# wendor_arduino.net
KiCad netlist of a schematic drawn in EAGLE
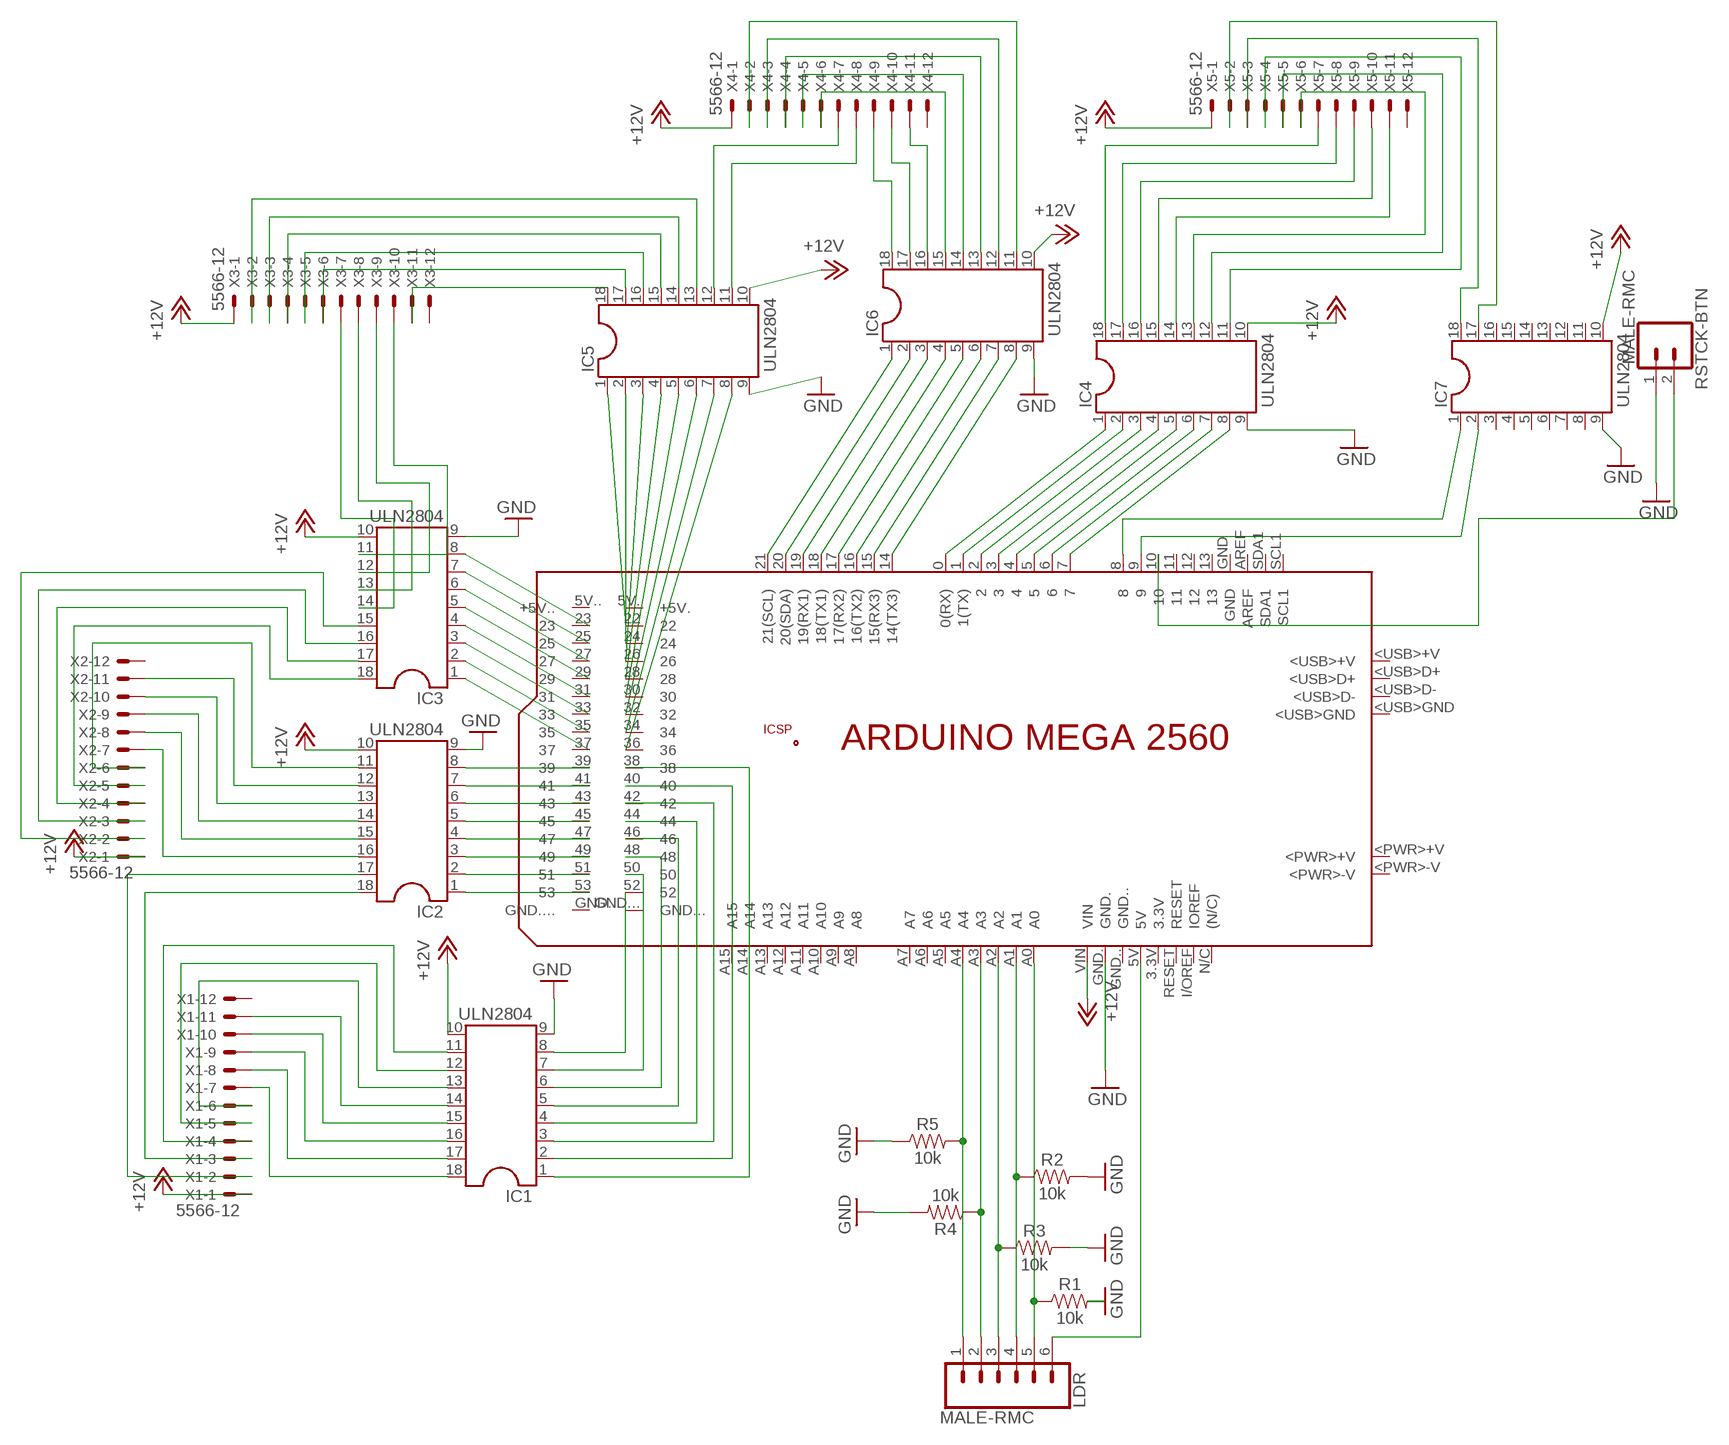
[diagram p0: schematic, sheet 1]

(export (version "E")
  (design (tool "Eeschema 10.0.6"))
  (components
    (comp (ref "IC1")
      (value "ULN2804")
      (footprint "eagle-import:SOCKET-18")
      (libsource (lib "eagle-import") (part "DIL18S"))
    )
    (comp (ref "IC2")
      (value "ULN2804")
      (footprint "eagle-import:SOCKET-18")
      (libsource (lib "eagle-import") (part "DIL18S"))
    )
    (comp (ref "IC3")
      (value "ULN2804")
      (footprint "eagle-import:SOCKET-18")
      (libsource (lib "eagle-import") (part "DIL18S"))
    )
    (comp (ref "IC4")
      (value "ULN2804")
      (footprint "eagle-import:SOCKET-18")
      (libsource (lib "eagle-import") (part "DIL18S"))
    )
    (comp (ref "IC5")
      (value "ULN2804")
      (footprint "eagle-import:SOCKET-18")
      (libsource (lib "eagle-import") (part "DIL18S"))
    )
    (comp (ref "IC6")
      (value "ULN2804")
      (footprint "eagle-import:SOCKET-18")
      (libsource (lib "eagle-import") (part "DIL18S"))
    )
    (comp (ref "IC7")
      (value "ULN2804")
      (footprint "eagle-import:SOCKET-18")
      (libsource (lib "eagle-import") (part "DIL18S"))
    )
    (comp (ref "LDR")
      (value "MALE-RMC")
      (footprint "eagle-import:1X06")
      (libsource (lib "eagle-import") (part "CONN_06SILK_FEMALE_PTH"))
    )
    (comp (ref "PCB1")
      (value "ARDUINO_MEGA2560")
      (footprint "eagle-import:ARDUINO_MEGA2560")
      (libsource (lib "eagle-import") (part "ARDUINO_MEGA2560"))
    )
    (comp (ref "R1")
      (value "10k")
      (footprint "eagle-import:AXIAL-0.3")
      (libsource (lib "eagle-import") (part "10KOHM-HORIZ-1/4W-1%"))
    )
    (comp (ref "R2")
      (value "10k")
      (footprint "eagle-import:AXIAL-0.3")
      (libsource (lib "eagle-import") (part "10KOHM-HORIZ-1/4W-1%"))
    )
    (comp (ref "R3")
      (value "10k")
      (footprint "eagle-import:AXIAL-0.3")
      (libsource (lib "eagle-import") (part "10KOHM-HORIZ-1/4W-1%"))
    )
    (comp (ref "R4")
      (value "10k")
      (footprint "eagle-import:AXIAL-0.3")
      (libsource (lib "eagle-import") (part "10KOHM-HORIZ-1/4W-1%"))
    )
    (comp (ref "R5")
      (value "10k")
      (footprint "eagle-import:AXIAL-0.3")
      (libsource (lib "eagle-import") (part "10KOHM-HORIZ-1/4W-1%"))
    )
    (comp (ref "RSTCK-BTN")
      (value "MALE-RMC")
      (footprint "eagle-import:1X02")
      (libsource (lib "eagle-import") (part "CONN_02"))
    )
    (comp (ref "X1")
      (value "5566-12")
      (footprint "eagle-import:5566-12")
      (fields (field (name "MF") "MOLEX"))
      (libsource (lib "eagle-import") (part "5566-12"))
    )
    (comp (ref "X2")
      (value "5566-12")
      (footprint "eagle-import:5566-12")
      (fields (field (name "MF") "MOLEX"))
      (libsource (lib "eagle-import") (part "5566-12"))
    )
    (comp (ref "X3")
      (value "5566-12")
      (footprint "eagle-import:5566-12")
      (fields (field (name "MF") "MOLEX"))
      (libsource (lib "eagle-import") (part "5566-12"))
    )
    (comp (ref "X4")
      (value "5566-12")
      (footprint "eagle-import:5566-12")
      (fields (field (name "MF") "MOLEX"))
      (libsource (lib "eagle-import") (part "5566-12"))
    )
    (comp (ref "X5")
      (value "5566-12")
      (footprint "eagle-import:5566-12")
      (fields (field (name "MF") "MOLEX"))
      (libsource (lib "eagle-import") (part "5566-12"))
    )
  )
  (nets
    (net (code "1") (name "+12V") (class "Default")
      (node (ref "IC1") (pin "10") (pinfunction "10_10") (pintype "passive"))
      (node (ref "IC2") (pin "10") (pinfunction "10_10") (pintype "passive"))
      (node (ref "IC3") (pin "10") (pinfunction "10_10") (pintype "passive"))
      (node (ref "IC4") (pin "10") (pinfunction "10_10") (pintype "passive"))
      (node (ref "IC5") (pin "10") (pinfunction "10_10") (pintype "passive"))
      (node (ref "IC6") (pin "10") (pinfunction "10_10") (pintype "passive"))
      (node (ref "IC7") (pin "10") (pinfunction "10_10") (pintype "passive"))
      (node (ref "PCB1") (pin "VIN") (pinfunction "VIN_VIN") (pintype "bidirectional"))
      (node (ref "X1") (pin "1") (pinfunction "S_1") (pintype "passive"))
      (node (ref "X2") (pin "1") (pinfunction "S_1") (pintype "passive"))
      (node (ref "X3") (pin "1") (pinfunction "S_1") (pintype "passive"))
      (node (ref "X4") (pin "1") (pinfunction "S_1") (pintype "passive"))
      (node (ref "X5") (pin "1") (pinfunction "S_1") (pintype "passive"))
    )
    (net (code "2") (name "GND") (class "Default")
      (node (ref "IC1") (pin "9") (pinfunction "9_9") (pintype "passive"))
      (node (ref "IC2") (pin "9") (pinfunction "9_9") (pintype "passive"))
      (node (ref "IC3") (pin "9") (pinfunction "9_9") (pintype "passive"))
      (node (ref "IC4") (pin "9") (pinfunction "9_9") (pintype "passive"))
      (node (ref "IC5") (pin "9") (pinfunction "9_9") (pintype "passive"))
      (node (ref "IC6") (pin "9") (pinfunction "9_9") (pintype "passive"))
      (node (ref "IC7") (pin "9") (pinfunction "9_9") (pintype "passive"))
      (node (ref "PCB1") (pin "GND.") (pinfunction "GND._GND.") (pintype "bidirectional"))
      (node (ref "R1") (pin "P$2") (pinfunction "2_P$2") (pintype "passive"))
      (node (ref "R2") (pin "P$2") (pinfunction "2_P$2") (pintype "passive"))
      (node (ref "R3") (pin "P$2") (pinfunction "2_P$2") (pintype "passive"))
      (node (ref "R4") (pin "P$2") (pinfunction "2_P$2") (pintype "passive"))
      (node (ref "R5") (pin "P$1") (pinfunction "1_P$1") (pintype "passive"))
      (node (ref "RSTCK-BTN") (pin "1") (pinfunction "1_1") (pintype "passive"))
    )
    (net (code "3") (name "Net-(IC1-Pad1)") (class "Default")
      (node (ref "IC1") (pin "1") (pinfunction "1_1") (pintype "passive"))
      (node (ref "PCB1") (pin "38") (pinfunction "38_38") (pintype "bidirectional"))
    )
    (net (code "4") (name "Net-(IC1-Pad2)") (class "Default")
      (node (ref "IC1") (pin "2") (pinfunction "2_2") (pintype "passive"))
      (node (ref "PCB1") (pin "40") (pinfunction "40_40") (pintype "bidirectional"))
    )
    (net (code "5") (name "Net-(IC1-Pad3)") (class "Default")
      (node (ref "IC1") (pin "3") (pinfunction "3_3") (pintype "passive"))
      (node (ref "PCB1") (pin "42") (pinfunction "42_42") (pintype "bidirectional"))
    )
    (net (code "6") (name "Net-(IC1-Pad4)") (class "Default")
      (node (ref "IC1") (pin "4") (pinfunction "4_4") (pintype "passive"))
      (node (ref "PCB1") (pin "44") (pinfunction "44_44") (pintype "bidirectional"))
    )
    (net (code "7") (name "Net-(IC1-Pad5)") (class "Default")
      (node (ref "IC1") (pin "5") (pinfunction "5_5") (pintype "passive"))
      (node (ref "PCB1") (pin "46") (pinfunction "46_46") (pintype "bidirectional"))
    )
    (net (code "8") (name "Net-(IC1-Pad6)") (class "Default")
      (node (ref "IC1") (pin "6") (pinfunction "6_6") (pintype "passive"))
      (node (ref "PCB1") (pin "48") (pinfunction "48_48") (pintype "bidirectional"))
    )
    (net (code "9") (name "Net-(IC1-Pad7)") (class "Default")
      (node (ref "IC1") (pin "7") (pinfunction "7_7") (pintype "passive"))
      (node (ref "PCB1") (pin "50") (pinfunction "50_50") (pintype "bidirectional"))
    )
    (net (code "10") (name "Net-(IC1-Pad8)") (class "Default")
      (node (ref "IC1") (pin "8") (pinfunction "8_8") (pintype "passive"))
      (node (ref "PCB1") (pin "52") (pinfunction "52_52") (pintype "bidirectional"))
    )
    (net (code "11") (name "Net-(IC2-Pad1)") (class "Default")
      (node (ref "IC2") (pin "1") (pinfunction "1_1") (pintype "passive"))
      (node (ref "PCB1") (pin "53") (pinfunction "53_53") (pintype "bidirectional"))
    )
    (net (code "12") (name "Net-(IC2-Pad2)") (class "Default")
      (node (ref "IC2") (pin "2") (pinfunction "2_2") (pintype "passive"))
      (node (ref "PCB1") (pin "51") (pinfunction "51_51") (pintype "bidirectional"))
    )
    (net (code "13") (name "Net-(IC2-Pad3)") (class "Default")
      (node (ref "IC2") (pin "3") (pinfunction "3_3") (pintype "passive"))
      (node (ref "PCB1") (pin "49") (pinfunction "49_49") (pintype "bidirectional"))
    )
    (net (code "14") (name "Net-(IC2-Pad4)") (class "Default")
      (node (ref "IC2") (pin "4") (pinfunction "4_4") (pintype "passive"))
      (node (ref "PCB1") (pin "47") (pinfunction "47_47") (pintype "bidirectional"))
    )
    (net (code "15") (name "Net-(IC2-Pad5)") (class "Default")
      (node (ref "IC2") (pin "5") (pinfunction "5_5") (pintype "passive"))
      (node (ref "PCB1") (pin "45") (pinfunction "45_45") (pintype "bidirectional"))
    )
    (net (code "16") (name "Net-(IC2-Pad6)") (class "Default")
      (node (ref "IC2") (pin "6") (pinfunction "6_6") (pintype "passive"))
      (node (ref "PCB1") (pin "43") (pinfunction "43_43") (pintype "bidirectional"))
    )
    (net (code "17") (name "Net-(IC2-Pad7)") (class "Default")
      (node (ref "IC2") (pin "7") (pinfunction "7_7") (pintype "passive"))
      (node (ref "PCB1") (pin "41") (pinfunction "41_41") (pintype "bidirectional"))
    )
    (net (code "18") (name "Net-(IC2-Pad8)") (class "Default")
      (node (ref "IC2") (pin "8") (pinfunction "8_8") (pintype "passive"))
      (node (ref "PCB1") (pin "39") (pinfunction "39_39") (pintype "bidirectional"))
    )
    (net (code "19") (name "Net-(IC3-Pad1)") (class "Default")
      (node (ref "IC3") (pin "1") (pinfunction "1_1") (pintype "passive"))
      (node (ref "PCB1") (pin "37") (pinfunction "37_37") (pintype "bidirectional"))
    )
    (net (code "20") (name "Net-(IC3-Pad2)") (class "Default")
      (node (ref "IC3") (pin "2") (pinfunction "2_2") (pintype "passive"))
      (node (ref "PCB1") (pin "35") (pinfunction "35_35") (pintype "bidirectional"))
    )
    (net (code "21") (name "Net-(IC3-Pad3)") (class "Default")
      (node (ref "IC3") (pin "3") (pinfunction "3_3") (pintype "passive"))
      (node (ref "PCB1") (pin "33") (pinfunction "33_33") (pintype "bidirectional"))
    )
    (net (code "22") (name "Net-(IC3-Pad4)") (class "Default")
      (node (ref "IC3") (pin "4") (pinfunction "4_4") (pintype "passive"))
      (node (ref "PCB1") (pin "31") (pinfunction "31_31") (pintype "bidirectional"))
    )
    (net (code "23") (name "Net-(IC3-Pad5)") (class "Default")
      (node (ref "IC3") (pin "5") (pinfunction "5_5") (pintype "passive"))
      (node (ref "PCB1") (pin "29") (pinfunction "29_29") (pintype "bidirectional"))
    )
    (net (code "24") (name "Net-(IC3-Pad6)") (class "Default")
      (node (ref "IC3") (pin "6") (pinfunction "6_6") (pintype "passive"))
      (node (ref "PCB1") (pin "27") (pinfunction "27_27") (pintype "bidirectional"))
    )
    (net (code "25") (name "Net-(IC3-Pad7)") (class "Default")
      (node (ref "IC3") (pin "7") (pinfunction "7_7") (pintype "passive"))
      (node (ref "PCB1") (pin "25") (pinfunction "25_25") (pintype "bidirectional"))
    )
    (net (code "26") (name "Net-(IC3-Pad8)") (class "Default")
      (node (ref "IC3") (pin "8") (pinfunction "8_8") (pintype "passive"))
      (node (ref "PCB1") (pin "23") (pinfunction "23_23") (pintype "bidirectional"))
    )
    (net (code "27") (name "Net-(IC4-Pad3)") (class "Default")
      (node (ref "IC4") (pin "3") (pinfunction "3_3") (pintype "passive"))
      (node (ref "PCB1") (pin "2") (pinfunction "2_2") (pintype "bidirectional"))
    )
    (net (code "28") (name "Net-(IC4-Pad4)") (class "Default")
      (node (ref "IC4") (pin "4") (pinfunction "4_4") (pintype "passive"))
      (node (ref "PCB1") (pin "3") (pinfunction "3_3") (pintype "bidirectional"))
    )
    (net (code "29") (name "Net-(IC4-Pad5)") (class "Default")
      (node (ref "IC4") (pin "5") (pinfunction "5_5") (pintype "passive"))
      (node (ref "PCB1") (pin "4") (pinfunction "4_4") (pintype "bidirectional"))
    )
    (net (code "30") (name "Net-(IC4-Pad6)") (class "Default")
      (node (ref "IC4") (pin "6") (pinfunction "6_6") (pintype "passive"))
      (node (ref "PCB1") (pin "5") (pinfunction "5_5") (pintype "bidirectional"))
    )
    (net (code "31") (name "Net-(IC4-Pad7)") (class "Default")
      (node (ref "IC4") (pin "7") (pinfunction "7_7") (pintype "passive"))
      (node (ref "PCB1") (pin "6") (pinfunction "6_6") (pintype "bidirectional"))
    )
    (net (code "32") (name "Net-(IC4-Pad8)") (class "Default")
      (node (ref "IC4") (pin "8") (pinfunction "8_8") (pintype "passive"))
      (node (ref "PCB1") (pin "7") (pinfunction "7_7") (pintype "bidirectional"))
    )
    (net (code "33") (name "Net-(IC5-Pad1)") (class "Default")
      (node (ref "IC5") (pin "1") (pinfunction "1_1") (pintype "passive"))
      (node (ref "PCB1") (pin "22") (pinfunction "22_22") (pintype "bidirectional"))
    )
    (net (code "34") (name "Net-(IC5-Pad2)") (class "Default")
      (node (ref "IC5") (pin "2") (pinfunction "2_2") (pintype "passive"))
      (node (ref "PCB1") (pin "24") (pinfunction "24_24") (pintype "bidirectional"))
    )
    (net (code "35") (name "Net-(IC5-Pad3)") (class "Default")
      (node (ref "IC5") (pin "3") (pinfunction "3_3") (pintype "passive"))
      (node (ref "PCB1") (pin "26") (pinfunction "26_26") (pintype "bidirectional"))
    )
    (net (code "36") (name "Net-(IC5-Pad4)") (class "Default")
      (node (ref "IC5") (pin "4") (pinfunction "4_4") (pintype "passive"))
      (node (ref "PCB1") (pin "28") (pinfunction "28_28") (pintype "bidirectional"))
    )
    (net (code "37") (name "Net-(IC5-Pad5)") (class "Default")
      (node (ref "IC5") (pin "5") (pinfunction "5_5") (pintype "passive"))
      (node (ref "PCB1") (pin "30") (pinfunction "30_30") (pintype "bidirectional"))
    )
    (net (code "38") (name "Net-(IC5-Pad6)") (class "Default")
      (node (ref "IC5") (pin "6") (pinfunction "6_6") (pintype "passive"))
      (node (ref "PCB1") (pin "32") (pinfunction "32_32") (pintype "bidirectional"))
    )
    (net (code "39") (name "Net-(IC5-Pad7)") (class "Default")
      (node (ref "IC5") (pin "7") (pinfunction "7_7") (pintype "passive"))
      (node (ref "PCB1") (pin "34") (pinfunction "34_34") (pintype "bidirectional"))
    )
    (net (code "40") (name "Net-(IC5-Pad8)") (class "Default")
      (node (ref "IC5") (pin "8") (pinfunction "8_8") (pintype "passive"))
      (node (ref "PCB1") (pin "36") (pinfunction "36_36") (pintype "bidirectional"))
    )
    (net (code "41") (name "Net-(IC7-Pad1)") (class "Default")
      (node (ref "IC7") (pin "1") (pinfunction "1_1") (pintype "passive"))
      (node (ref "PCB1") (pin "8") (pinfunction "8_8") (pintype "bidirectional"))
    )
    (net (code "42") (name "Net-(IC7-Pad2)") (class "Default")
      (node (ref "IC7") (pin "2") (pinfunction "2_2") (pintype "passive"))
      (node (ref "PCB1") (pin "9") (pinfunction "9_9") (pintype "bidirectional"))
    )
    (net (code "43") (name "Net-(LDR-Pad6)") (class "Default")
      (node (ref "LDR") (pin "6") (pinfunction "6_6") (pintype "passive"))
      (node (ref "PCB1") (pin "5V") (pinfunction "5V_5V") (pintype "bidirectional"))
    )
    (net (code "44") (name "Net-(PCB1-0(RX))") (class "Default")
      (node (ref "IC4") (pin "1") (pinfunction "1_1") (pintype "passive"))
      (node (ref "PCB1") (pin "0") (pinfunction "0(RX)_0") (pintype "bidirectional"))
    )
    (net (code "45") (name "Net-(PCB1-1(TX))") (class "Default")
      (node (ref "IC4") (pin "2") (pinfunction "2_2") (pintype "passive"))
      (node (ref "PCB1") (pin "1") (pinfunction "1(TX)_1") (pintype "bidirectional"))
    )
    (net (code "46") (name "Net-(PCB1-14(TX3))") (class "Default")
      (node (ref "IC6") (pin "8") (pinfunction "8_8") (pintype "passive"))
      (node (ref "PCB1") (pin "14") (pinfunction "14(TX3)_14") (pintype "bidirectional"))
    )
    (net (code "47") (name "Net-(PCB1-15(RX3))") (class "Default")
      (node (ref "IC6") (pin "7") (pinfunction "7_7") (pintype "passive"))
      (node (ref "PCB1") (pin "15") (pinfunction "15(RX3)_15") (pintype "bidirectional"))
    )
    (net (code "48") (name "Net-(PCB1-16(TX2))") (class "Default")
      (node (ref "IC6") (pin "6") (pinfunction "6_6") (pintype "passive"))
      (node (ref "PCB1") (pin "16") (pinfunction "16(TX2)_16") (pintype "bidirectional"))
    )
    (net (code "49") (name "Net-(PCB1-17(RX2))") (class "Default")
      (node (ref "IC6") (pin "5") (pinfunction "5_5") (pintype "passive"))
      (node (ref "PCB1") (pin "17") (pinfunction "17(RX2)_17") (pintype "bidirectional"))
    )
    (net (code "50") (name "Net-(PCB1-18(TX1))") (class "Default")
      (node (ref "IC6") (pin "4") (pinfunction "4_4") (pintype "passive"))
      (node (ref "PCB1") (pin "18") (pinfunction "18(TX1)_18") (pintype "bidirectional"))
    )
    (net (code "51") (name "Net-(PCB1-19(RX1))") (class "Default")
      (node (ref "IC6") (pin "3") (pinfunction "3_3") (pintype "passive"))
      (node (ref "PCB1") (pin "19") (pinfunction "19(RX1)_19") (pintype "bidirectional"))
    )
    (net (code "52") (name "Net-(PCB1-20(SDA))") (class "Default")
      (node (ref "IC6") (pin "2") (pinfunction "2_2") (pintype "passive"))
      (node (ref "PCB1") (pin "20") (pinfunction "20(SDA)_20") (pintype "bidirectional"))
    )
    (net (code "53") (name "Net-(PCB1-21(SCL))") (class "Default")
      (node (ref "IC6") (pin "1") (pinfunction "1_1") (pintype "passive"))
      (node (ref "PCB1") (pin "21") (pinfunction "21(SCL)_21") (pintype "bidirectional"))
    )
    (net (code "54") (name "Net-(PCB1-Pad10)") (class "Default")
      (node (ref "PCB1") (pin "10") (pinfunction "10_10") (pintype "bidirectional"))
      (node (ref "RSTCK-BTN") (pin "2") (pinfunction "2_2") (pintype "passive"))
    )
    (net (code "55") (name "Net-(R1-1)") (class "Default")
      (node (ref "LDR") (pin "5") (pinfunction "5_5") (pintype "passive"))
      (node (ref "PCB1") (pin "A0") (pinfunction "A0_A0") (pintype "bidirectional"))
      (node (ref "R1") (pin "P$1") (pinfunction "1_P$1") (pintype "passive"))
    )
    (net (code "56") (name "Net-(R2-1)") (class "Default")
      (node (ref "LDR") (pin "4") (pinfunction "4_4") (pintype "passive"))
      (node (ref "PCB1") (pin "A1") (pinfunction "A1_A1") (pintype "bidirectional"))
      (node (ref "R2") (pin "P$1") (pinfunction "1_P$1") (pintype "passive"))
    )
    (net (code "57") (name "Net-(R3-1)") (class "Default")
      (node (ref "LDR") (pin "3") (pinfunction "3_3") (pintype "passive"))
      (node (ref "PCB1") (pin "A2") (pinfunction "A2_A2") (pintype "bidirectional"))
      (node (ref "R3") (pin "P$1") (pinfunction "1_P$1") (pintype "passive"))
    )
    (net (code "58") (name "Net-(R4-1)") (class "Default")
      (node (ref "LDR") (pin "2") (pinfunction "2_2") (pintype "passive"))
      (node (ref "PCB1") (pin "A3") (pinfunction "A3_A3") (pintype "bidirectional"))
      (node (ref "R4") (pin "P$1") (pinfunction "1_P$1") (pintype "passive"))
    )
    (net (code "59") (name "Net-(R5-2)") (class "Default")
      (node (ref "LDR") (pin "1") (pinfunction "1_1") (pintype "passive"))
      (node (ref "PCB1") (pin "A4") (pinfunction "A4_A4") (pintype "bidirectional"))
      (node (ref "R5") (pin "P$2") (pinfunction "2_P$2") (pintype "passive"))
    )
    (net (code "60") (name "Net-(X1B-S)") (class "Default")
      (node (ref "IC1") (pin "15") (pinfunction "15_15") (pintype "passive"))
      (node (ref "X1") (pin "10") (pinfunction "S_10") (pintype "passive"))
    )
    (net (code "61") (name "Net-(X1C-S)") (class "Default")
      (node (ref "IC1") (pin "14") (pinfunction "14_14") (pintype "passive"))
      (node (ref "X1") (pin "11") (pinfunction "S_11") (pintype "passive"))
    )
    (net (code "62") (name "Net-(X1E-S)") (class "Default")
      (node (ref "IC2") (pin "17") (pinfunction "17_17") (pintype "passive"))
      (node (ref "X1") (pin "2") (pinfunction "S_2") (pintype "passive"))
    )
    (net (code "63") (name "Net-(X1F-S)") (class "Default")
      (node (ref "IC2") (pin "18") (pinfunction "18_18") (pintype "passive"))
      (node (ref "X1") (pin "3") (pinfunction "S_3") (pintype "passive"))
    )
    (net (code "64") (name "Net-(X1G-S)") (class "Default")
      (node (ref "IC1") (pin "11") (pinfunction "11_11") (pintype "passive"))
      (node (ref "X1") (pin "4") (pinfunction "S_4") (pintype "passive"))
    )
    (net (code "65") (name "Net-(X1H-S)") (class "Default")
      (node (ref "IC1") (pin "12") (pinfunction "12_12") (pintype "passive"))
      (node (ref "X1") (pin "5") (pinfunction "S_5") (pintype "passive"))
    )
    (net (code "66") (name "Net-(X1I-S)") (class "Default")
      (node (ref "IC1") (pin "13") (pinfunction "13_13") (pintype "passive"))
      (node (ref "X1") (pin "6") (pinfunction "S_6") (pintype "passive"))
    )
    (net (code "67") (name "Net-(X1J-S)") (class "Default")
      (node (ref "IC1") (pin "18") (pinfunction "18_18") (pintype "passive"))
      (node (ref "X1") (pin "7") (pinfunction "S_7") (pintype "passive"))
    )
    (net (code "68") (name "Net-(X1K-S)") (class "Default")
      (node (ref "IC1") (pin "17") (pinfunction "17_17") (pintype "passive"))
      (node (ref "X1") (pin "8") (pinfunction "S_8") (pintype "passive"))
    )
    (net (code "69") (name "Net-(X1L-S)") (class "Default")
      (node (ref "IC1") (pin "16") (pinfunction "16_16") (pintype "passive"))
      (node (ref "X1") (pin "9") (pinfunction "S_9") (pintype "passive"))
    )
    (net (code "70") (name "Net-(X2B-S)") (class "Default")
      (node (ref "IC2") (pin "13") (pinfunction "13_13") (pintype "passive"))
      (node (ref "X2") (pin "10") (pinfunction "S_10") (pintype "passive"))
    )
    (net (code "71") (name "Net-(X2C-S)") (class "Default")
      (node (ref "IC2") (pin "12") (pinfunction "12_12") (pintype "passive"))
      (node (ref "X2") (pin "11") (pinfunction "S_11") (pintype "passive"))
    )
    (net (code "72") (name "Net-(X2E-S)") (class "Default")
      (node (ref "IC3") (pin "15") (pinfunction "15_15") (pintype "passive"))
      (node (ref "X2") (pin "2") (pinfunction "S_2") (pintype "passive"))
    )
    (net (code "73") (name "Net-(X2F-S)") (class "Default")
      (node (ref "IC3") (pin "16") (pinfunction "16_16") (pintype "passive"))
      (node (ref "X2") (pin "3") (pinfunction "S_3") (pintype "passive"))
    )
    (net (code "74") (name "Net-(X2G-S)") (class "Default")
      (node (ref "IC3") (pin "17") (pinfunction "17_17") (pintype "passive"))
      (node (ref "X2") (pin "4") (pinfunction "S_4") (pintype "passive"))
    )
    (net (code "75") (name "Net-(X2H-S)") (class "Default")
      (node (ref "IC3") (pin "18") (pinfunction "18_18") (pintype "passive"))
      (node (ref "X2") (pin "5") (pinfunction "S_5") (pintype "passive"))
    )
    (net (code "76") (name "Net-(X2I-S)") (class "Default")
      (node (ref "IC2") (pin "11") (pinfunction "11_11") (pintype "passive"))
      (node (ref "X2") (pin "6") (pinfunction "S_6") (pintype "passive"))
    )
    (net (code "77") (name "Net-(X2J-S)") (class "Default")
      (node (ref "IC2") (pin "16") (pinfunction "16_16") (pintype "passive"))
      (node (ref "X2") (pin "7") (pinfunction "S_7") (pintype "passive"))
    )
    (net (code "78") (name "Net-(X2K-S)") (class "Default")
      (node (ref "IC2") (pin "15") (pinfunction "15_15") (pintype "passive"))
      (node (ref "X2") (pin "8") (pinfunction "S_8") (pintype "passive"))
    )
    (net (code "79") (name "Net-(X2L-S)") (class "Default")
      (node (ref "IC2") (pin "14") (pinfunction "14_14") (pintype "passive"))
      (node (ref "X2") (pin "9") (pinfunction "S_9") (pintype "passive"))
    )
    (net (code "80") (name "Net-(X3B-S)") (class "Default")
      (node (ref "IC3") (pin "11") (pinfunction "11_11") (pintype "passive"))
      (node (ref "X3") (pin "10") (pinfunction "S_10") (pintype "passive"))
    )
    (net (code "81") (name "Net-(X3C-S)") (class "Default")
      (node (ref "IC5") (pin "18") (pinfunction "18_18") (pintype "passive"))
      (node (ref "X3") (pin "11") (pinfunction "S_11") (pintype "passive"))
    )
    (net (code "82") (name "Net-(X3E-S)") (class "Default")
      (node (ref "IC5") (pin "13") (pinfunction "13_13") (pintype "passive"))
      (node (ref "X3") (pin "2") (pinfunction "S_2") (pintype "passive"))
    )
    (net (code "83") (name "Net-(X3F-S)") (class "Default")
      (node (ref "IC5") (pin "14") (pinfunction "14_14") (pintype "passive"))
      (node (ref "X3") (pin "3") (pinfunction "S_3") (pintype "passive"))
    )
    (net (code "84") (name "Net-(X3G-S)") (class "Default")
      (node (ref "IC5") (pin "15") (pinfunction "15_15") (pintype "passive"))
      (node (ref "X3") (pin "4") (pinfunction "S_4") (pintype "passive"))
    )
    (net (code "85") (name "Net-(X3H-S)") (class "Default")
      (node (ref "IC5") (pin "16") (pinfunction "16_16") (pintype "passive"))
      (node (ref "X3") (pin "5") (pinfunction "S_5") (pintype "passive"))
    )
    (net (code "86") (name "Net-(X3I-S)") (class "Default")
      (node (ref "IC5") (pin "17") (pinfunction "17_17") (pintype "passive"))
      (node (ref "X3") (pin "6") (pinfunction "S_6") (pintype "passive"))
    )
    (net (code "87") (name "Net-(X3J-S)") (class "Default")
      (node (ref "IC3") (pin "14") (pinfunction "14_14") (pintype "passive"))
      (node (ref "X3") (pin "7") (pinfunction "S_7") (pintype "passive"))
    )
    (net (code "88") (name "Net-(X3K-S)") (class "Default")
      (node (ref "IC3") (pin "13") (pinfunction "13_13") (pintype "passive"))
      (node (ref "X3") (pin "8") (pinfunction "S_8") (pintype "passive"))
    )
    (net (code "89") (name "Net-(X3L-S)") (class "Default")
      (node (ref "IC3") (pin "12") (pinfunction "12_12") (pintype "passive"))
      (node (ref "X3") (pin "9") (pinfunction "S_9") (pintype "passive"))
    )
    (net (code "90") (name "Net-(X4B-S)") (class "Default")
      (node (ref "IC6") (pin "17") (pinfunction "17_17") (pintype "passive"))
      (node (ref "X4") (pin "10") (pinfunction "S_10") (pintype "passive"))
    )
    (net (code "91") (name "Net-(X4C-S)") (class "Default")
      (node (ref "IC6") (pin "16") (pinfunction "16_16") (pintype "passive"))
      (node (ref "X4") (pin "11") (pinfunction "S_11") (pintype "passive"))
    )
    (net (code "92") (name "Net-(X4E-S)") (class "Default")
      (node (ref "IC6") (pin "11") (pinfunction "11_11") (pintype "passive"))
      (node (ref "X4") (pin "2") (pinfunction "S_2") (pintype "passive"))
    )
    (net (code "93") (name "Net-(X4F-S)") (class "Default")
      (node (ref "IC6") (pin "12") (pinfunction "12_12") (pintype "passive"))
      (node (ref "X4") (pin "3") (pinfunction "S_3") (pintype "passive"))
    )
    (net (code "94") (name "Net-(X4G-S)") (class "Default")
      (node (ref "IC6") (pin "13") (pinfunction "13_13") (pintype "passive"))
      (node (ref "X4") (pin "4") (pinfunction "S_4") (pintype "passive"))
    )
    (net (code "95") (name "Net-(X4H-S)") (class "Default")
      (node (ref "IC6") (pin "14") (pinfunction "14_14") (pintype "passive"))
      (node (ref "X4") (pin "5") (pinfunction "S_5") (pintype "passive"))
    )
    (net (code "96") (name "Net-(X4I-S)") (class "Default")
      (node (ref "IC6") (pin "15") (pinfunction "15_15") (pintype "passive"))
      (node (ref "X4") (pin "6") (pinfunction "S_6") (pintype "passive"))
    )
    (net (code "97") (name "Net-(X4J-S)") (class "Default")
      (node (ref "IC5") (pin "12") (pinfunction "12_12") (pintype "passive"))
      (node (ref "X4") (pin "7") (pinfunction "S_7") (pintype "passive"))
    )
    (net (code "98") (name "Net-(X4K-S)") (class "Default")
      (node (ref "IC5") (pin "11") (pinfunction "11_11") (pintype "passive"))
      (node (ref "X4") (pin "8") (pinfunction "S_8") (pintype "passive"))
    )
    (net (code "99") (name "Net-(X4L-S)") (class "Default")
      (node (ref "IC6") (pin "18") (pinfunction "18_18") (pintype "passive"))
      (node (ref "X4") (pin "9") (pinfunction "S_9") (pintype "passive"))
    )
    (net (code "100") (name "Net-(X5B-S)") (class "Default")
      (node (ref "IC4") (pin "15") (pinfunction "15_15") (pintype "passive"))
      (node (ref "X5") (pin "10") (pinfunction "S_10") (pintype "passive"))
    )
    (net (code "101") (name "Net-(X5C-S)") (class "Default")
      (node (ref "IC4") (pin "14") (pinfunction "14_14") (pintype "passive"))
      (node (ref "X5") (pin "11") (pinfunction "S_11") (pintype "passive"))
    )
    (net (code "102") (name "Net-(X5E-S)") (class "Default")
      (node (ref "IC7") (pin "17") (pinfunction "17_17") (pintype "passive"))
      (node (ref "X5") (pin "2") (pinfunction "S_2") (pintype "passive"))
    )
    (net (code "103") (name "Net-(X5F-S)") (class "Default")
      (node (ref "IC7") (pin "18") (pinfunction "18_18") (pintype "passive"))
      (node (ref "X5") (pin "3") (pinfunction "S_3") (pintype "passive"))
    )
    (net (code "104") (name "Net-(X5G-S)") (class "Default")
      (node (ref "IC4") (pin "11") (pinfunction "11_11") (pintype "passive"))
      (node (ref "X5") (pin "4") (pinfunction "S_4") (pintype "passive"))
    )
    (net (code "105") (name "Net-(X5H-S)") (class "Default")
      (node (ref "IC4") (pin "12") (pinfunction "12_12") (pintype "passive"))
      (node (ref "X5") (pin "5") (pinfunction "S_5") (pintype "passive"))
    )
    (net (code "106") (name "Net-(X5I-S)") (class "Default")
      (node (ref "IC4") (pin "13") (pinfunction "13_13") (pintype "passive"))
      (node (ref "X5") (pin "6") (pinfunction "S_6") (pintype "passive"))
    )
    (net (code "107") (name "Net-(X5J-S)") (class "Default")
      (node (ref "IC4") (pin "18") (pinfunction "18_18") (pintype "passive"))
      (node (ref "X5") (pin "7") (pinfunction "S_7") (pintype "passive"))
    )
    (net (code "108") (name "Net-(X5K-S)") (class "Default")
      (node (ref "IC4") (pin "17") (pinfunction "17_17") (pintype "passive"))
      (node (ref "X5") (pin "8") (pinfunction "S_8") (pintype "passive"))
    )
    (net (code "109") (name "Net-(X5L-S)") (class "Default")
      (node (ref "IC4") (pin "16") (pinfunction "16_16") (pintype "passive"))
      (node (ref "X5") (pin "9") (pinfunction "S_9") (pintype "passive"))
    )
    (net (code "110") (name "unconnected-(IC7-Pad3)") (class "Default")
      (node (ref "IC7") (pin "3") (pinfunction "3_3") (pintype "passive"))
    )
    (net (code "111") (name "unconnected-(IC7-Pad4)") (class "Default")
      (node (ref "IC7") (pin "4") (pinfunction "4_4") (pintype "passive"))
    )
    (net (code "112") (name "unconnected-(IC7-Pad5)") (class "Default")
      (node (ref "IC7") (pin "5") (pinfunction "5_5") (pintype "passive"))
    )
    (net (code "113") (name "unconnected-(IC7-Pad6)") (class "Default")
      (node (ref "IC7") (pin "6") (pinfunction "6_6") (pintype "passive"))
    )
    (net (code "114") (name "unconnected-(IC7-Pad7)") (class "Default")
      (node (ref "IC7") (pin "7") (pinfunction "7_7") (pintype "passive"))
    )
    (net (code "115") (name "unconnected-(IC7-Pad8)") (class "Default")
      (node (ref "IC7") (pin "8") (pinfunction "8_8") (pintype "passive"))
    )
    (net (code "116") (name "unconnected-(IC7-Pad11)") (class "Default")
      (node (ref "IC7") (pin "11") (pinfunction "11_11") (pintype "passive"))
    )
    (net (code "117") (name "unconnected-(IC7-Pad12)") (class "Default")
      (node (ref "IC7") (pin "12") (pinfunction "12_12") (pintype "passive"))
    )
    (net (code "118") (name "unconnected-(IC7-Pad13)") (class "Default")
      (node (ref "IC7") (pin "13") (pinfunction "13_13") (pintype "passive"))
    )
    (net (code "119") (name "unconnected-(IC7-Pad14)") (class "Default")
      (node (ref "IC7") (pin "14") (pinfunction "14_14") (pintype "passive"))
    )
    (net (code "120") (name "unconnected-(IC7-Pad15)") (class "Default")
      (node (ref "IC7") (pin "15") (pinfunction "15_15") (pintype "passive"))
    )
    (net (code "121") (name "unconnected-(IC7-Pad16)") (class "Default")
      (node (ref "IC7") (pin "16") (pinfunction "16_16") (pintype "passive"))
    )
    (net (code "122") (name "unconnected-(PCB1-(N{slash}C)-PadN{slash}C)") (class "Default")
      (node (ref "PCB1") (pin "N/C") (pinfunction "(N/C)_N/C") (pintype "bidirectional"))
    )
    (net (code "123") (name "unconnected-(PCB1-+5V.-Pad5V.)") (class "Default")
      (node (ref "PCB1") (pin "5V.") (pinfunction "+5V._5V.") (pintype "bidirectional"))
    )
    (net (code "124") (name "unconnected-(PCB1-+5V..-Pad5V..)") (class "Default")
      (node (ref "PCB1") (pin "5V..") (pinfunction "+5V.._5V..") (pintype "bidirectional"))
    )
    (net (code "125") (name "unconnected-(PCB1-IOREF-PadI{slash}OREF)") (class "Default")
      (node (ref "PCB1") (pin "I/OREF") (pinfunction "IOREF_I/OREF") (pintype "bidirectional"))
    )
    (net (code "126") (name "unconnected-(PCB1-Pad+5V_)") (class "Default")
      (node (ref "PCB1") (pin "+5V_") (pinfunction "+5V__+5V_") (pintype "bidirectional"))
    )
    (net (code "127") (name "unconnected-(PCB1-Pad3.3V)") (class "Default")
      (node (ref "PCB1") (pin "3.3V") (pinfunction "3.3V_3.3V") (pintype "bidirectional"))
    )
    (net (code "128") (name "unconnected-(PCB1-Pad11)") (class "Default")
      (node (ref "PCB1") (pin "11") (pinfunction "11_11") (pintype "bidirectional"))
    )
    (net (code "129") (name "unconnected-(PCB1-Pad12)") (class "Default")
      (node (ref "PCB1") (pin "12") (pinfunction "12_12") (pintype "bidirectional"))
    )
    (net (code "130") (name "unconnected-(PCB1-Pad13)") (class "Default")
      (node (ref "PCB1") (pin "13") (pinfunction "13_13") (pintype "bidirectional"))
    )
    (net (code "131") (name "unconnected-(PCB1-Pad<PWR>+V)") (class "Default")
      (node (ref "PCB1") (pin "<PWR>+V") (pinfunction "<PWR>+V_<PWR>+V") (pintype "no_connect"))
    )
    (net (code "132") (name "unconnected-(PCB1-Pad<PWR>-V)") (class "Default")
      (node (ref "PCB1") (pin "<PWR>-V") (pinfunction "<PWR>-V_<PWR>-V") (pintype "no_connect"))
    )
    (net (code "133") (name "unconnected-(PCB1-Pad<USB>+V)") (class "Default")
      (node (ref "PCB1") (pin "<USB>+V") (pinfunction "<USB>+V_<USB>+V") (pintype "no_connect"))
    )
    (net (code "134") (name "unconnected-(PCB1-Pad<USB>D+)") (class "Default")
      (node (ref "PCB1") (pin "<USB>D+") (pinfunction "<USB>D+_<USB>D+") (pintype "no_connect"))
    )
    (net (code "135") (name "unconnected-(PCB1-Pad<USB>D-)") (class "Default")
      (node (ref "PCB1") (pin "<USB>D-") (pinfunction "<USB>D-_<USB>D-") (pintype "no_connect"))
    )
    (net (code "136") (name "unconnected-(PCB1-Pad<USB>GND)") (class "Default")
      (node (ref "PCB1") (pin "<USB>GND") (pinfunction "<USB>GND_<USB>GND") (pintype "no_connect"))
    )
    (net (code "137") (name "unconnected-(PCB1-PadA5)") (class "Default")
      (node (ref "PCB1") (pin "A5") (pinfunction "A5_A5") (pintype "bidirectional"))
    )
    (net (code "138") (name "unconnected-(PCB1-PadA6)") (class "Default")
      (node (ref "PCB1") (pin "A6") (pinfunction "A6_A6") (pintype "bidirectional"))
    )
    (net (code "139") (name "unconnected-(PCB1-PadA7)") (class "Default")
      (node (ref "PCB1") (pin "A7") (pinfunction "A7_A7") (pintype "bidirectional"))
    )
    (net (code "140") (name "unconnected-(PCB1-PadA8)") (class "Default")
      (node (ref "PCB1") (pin "A8") (pinfunction "A8_A8") (pintype "bidirectional"))
    )
    (net (code "141") (name "unconnected-(PCB1-PadA9)") (class "Default")
      (node (ref "PCB1") (pin "A9") (pinfunction "A9_A9") (pintype "bidirectional"))
    )
    (net (code "142") (name "unconnected-(PCB1-PadA10)") (class "Default")
      (node (ref "PCB1") (pin "A10") (pinfunction "A10_A10") (pintype "bidirectional"))
    )
    (net (code "143") (name "unconnected-(PCB1-PadA11)") (class "Default")
      (node (ref "PCB1") (pin "A11") (pinfunction "A11_A11") (pintype "bidirectional"))
    )
    (net (code "144") (name "unconnected-(PCB1-PadA12)") (class "Default")
      (node (ref "PCB1") (pin "A12") (pinfunction "A12_A12") (pintype "bidirectional"))
    )
    (net (code "145") (name "unconnected-(PCB1-PadA13)") (class "Default")
      (node (ref "PCB1") (pin "A13") (pinfunction "A13_A13") (pintype "bidirectional"))
    )
    (net (code "146") (name "unconnected-(PCB1-PadA14)") (class "Default")
      (node (ref "PCB1") (pin "A14") (pinfunction "A14_A14") (pintype "bidirectional"))
    )
    (net (code "147") (name "unconnected-(PCB1-PadA15)") (class "Default")
      (node (ref "PCB1") (pin "A15") (pinfunction "A15_A15") (pintype "bidirectional"))
    )
    (net (code "148") (name "unconnected-(PCB1-PadAREF)") (class "Default")
      (node (ref "PCB1") (pin "AREF") (pinfunction "AREF_AREF") (pintype "bidirectional"))
    )
    (net (code "149") (name "unconnected-(PCB1-PadGND)") (class "Default")
      (node (ref "PCB1") (pin "GND") (pinfunction "GND_GND") (pintype "bidirectional"))
    )
    (net (code "150") (name "unconnected-(PCB1-PadGND..)") (class "Default")
      (node (ref "PCB1") (pin "GND..") (pinfunction "GND.._GND..") (pintype "bidirectional"))
    )
    (net (code "151") (name "unconnected-(PCB1-PadGND...)") (class "Default")
      (node (ref "PCB1") (pin "GND...") (pinfunction "GND..._GND...") (pintype "bidirectional"))
    )
    (net (code "152") (name "unconnected-(PCB1-PadGND....)") (class "Default")
      (node (ref "PCB1") (pin "GND....") (pinfunction "GND...._GND....") (pintype "bidirectional"))
    )
    (net (code "153") (name "unconnected-(PCB1-PadGND__)") (class "Default")
      (node (ref "PCB1") (pin "GND__") (pinfunction "GND___GND__") (pintype "bidirectional"))
    )
    (net (code "154") (name "unconnected-(PCB1-PadMISO)") (class "Default")
      (node (ref "PCB1") (pin "MISO") (pinfunction "MISO_MISO") (pintype "bidirectional"))
    )
    (net (code "155") (name "unconnected-(PCB1-PadMOSI)") (class "Default")
      (node (ref "PCB1") (pin "MOSI") (pinfunction "MOSI_MOSI") (pintype "bidirectional"))
    )
    (net (code "156") (name "unconnected-(PCB1-PadRESET)") (class "Default")
      (node (ref "PCB1") (pin "RESET") (pinfunction "RESET_RESET") (pintype "bidirectional"))
    )
    (net (code "157") (name "unconnected-(PCB1-PadRESET.)") (class "Default")
      (node (ref "PCB1") (pin "RESET.") (pinfunction "RESET._RESET.") (pintype "bidirectional"))
    )
    (net (code "158") (name "unconnected-(PCB1-PadSCK)") (class "Default")
      (node (ref "PCB1") (pin "SCK") (pinfunction "SCK_SCK") (pintype "bidirectional"))
    )
    (net (code "159") (name "unconnected-(PCB1-PadSCL1)") (class "Default")
      (node (ref "PCB1") (pin "SCL1") (pinfunction "SCL1_SCL1") (pintype "bidirectional"))
    )
    (net (code "160") (name "unconnected-(PCB1-PadSDA1)") (class "Default")
      (node (ref "PCB1") (pin "SDA1") (pinfunction "SDA1_SDA1") (pintype "bidirectional"))
    )
    (net (code "161") (name "unconnected-(X1D-S-Pad12)") (class "Default")
      (node (ref "X1") (pin "12") (pinfunction "S_12") (pintype "passive"))
    )
    (net (code "162") (name "unconnected-(X2D-S-Pad12)") (class "Default")
      (node (ref "X2") (pin "12") (pinfunction "S_12") (pintype "passive"))
    )
    (net (code "163") (name "unconnected-(X3D-S-Pad12)") (class "Default")
      (node (ref "X3") (pin "12") (pinfunction "S_12") (pintype "passive"))
    )
    (net (code "164") (name "unconnected-(X4D-S-Pad12)") (class "Default")
      (node (ref "X4") (pin "12") (pinfunction "S_12") (pintype "passive"))
    )
    (net (code "165") (name "unconnected-(X5D-S-Pad12)") (class "Default")
      (node (ref "X5") (pin "12") (pinfunction "S_12") (pintype "passive"))
    )
  )
)
